# 07_FPGA_banks_3_4_5.net
KiCad netlist of a schematic drawn in Altium Designer
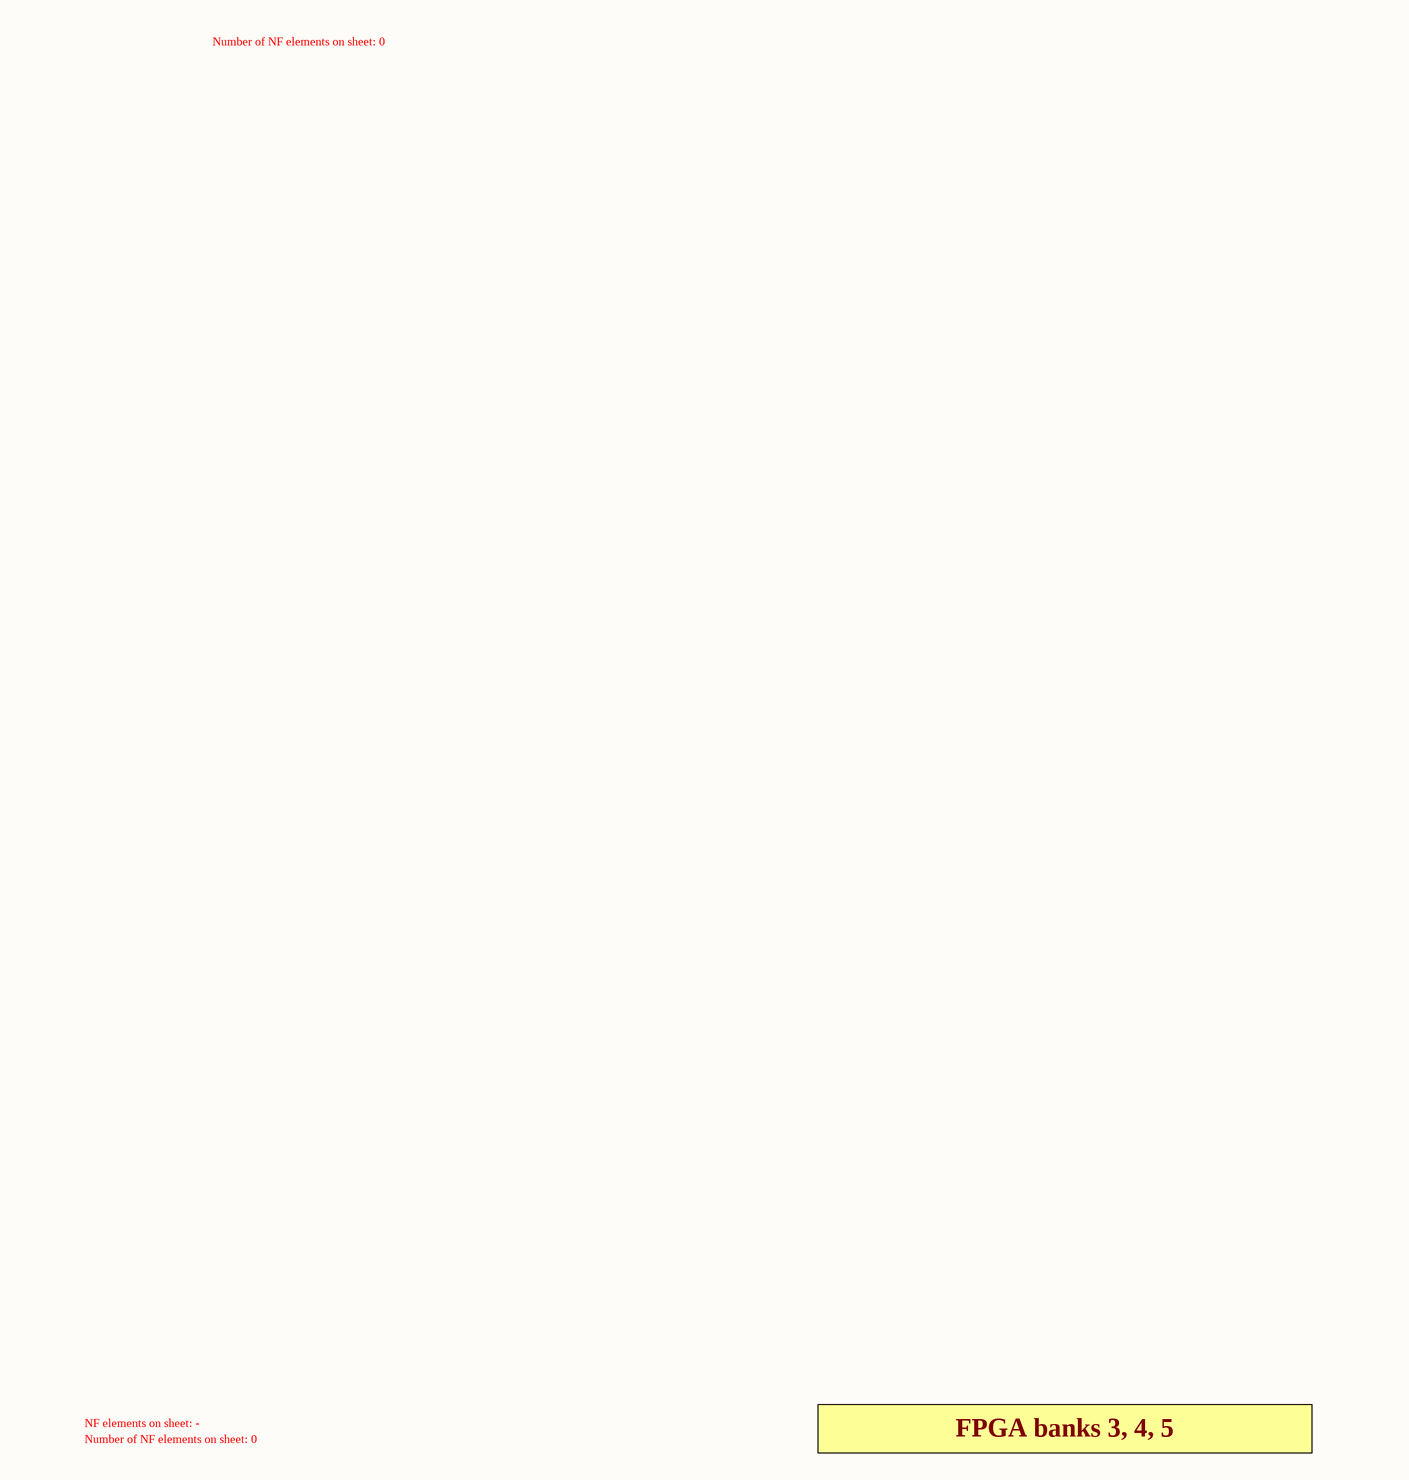
[diagram p0: 07_FPGA_banks_3_4_5.SchDoc, top]
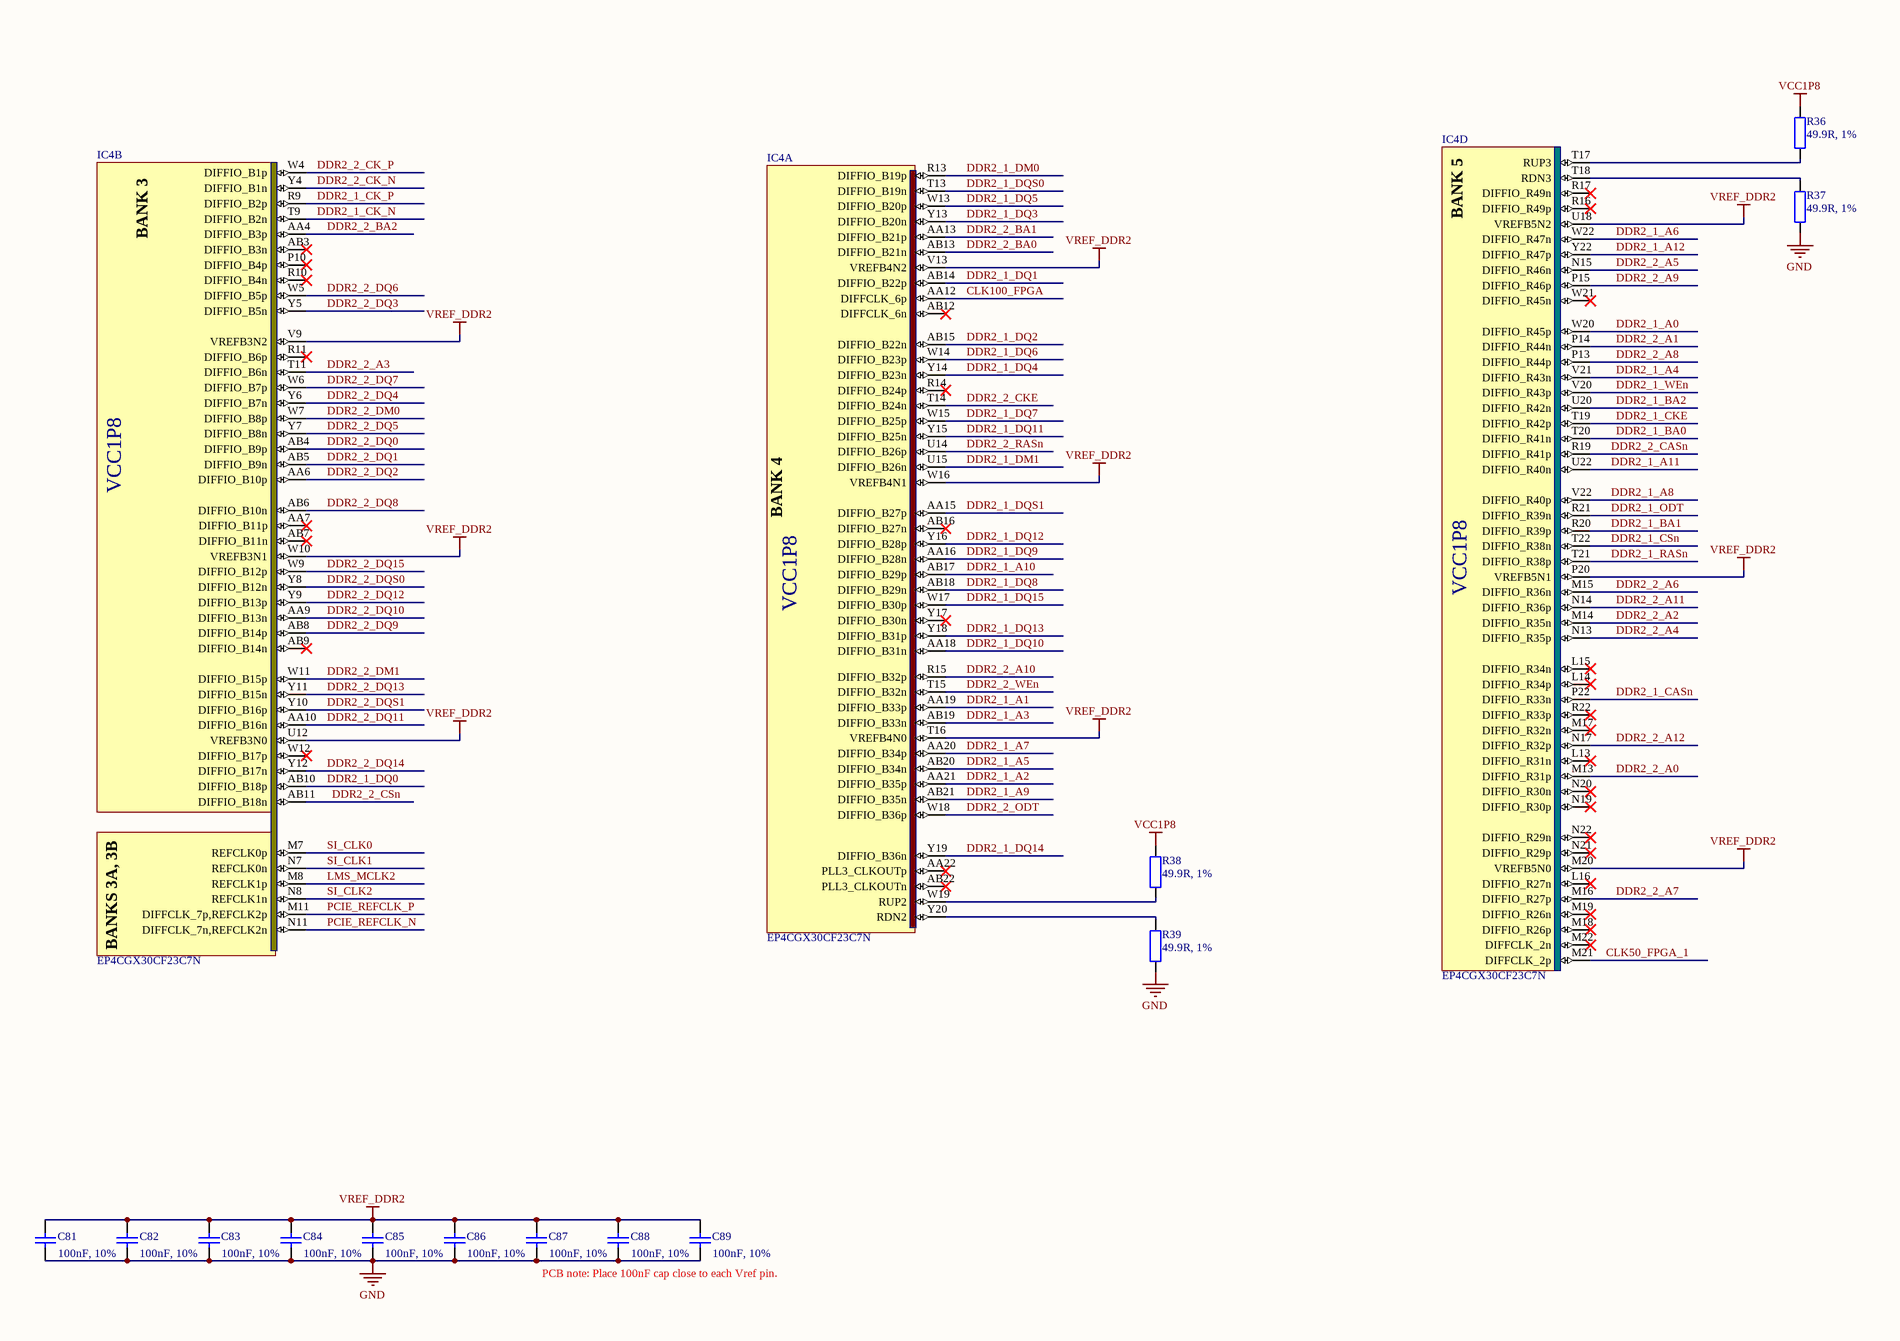
[diagram p1: 07_FPGA_banks_3_4_5.SchDoc, bottom]

(export (version "E")
  (design (tool "Eeschema 10.0.6"))
  (components
    (comp (ref "C81")
      (value "100nF, 10%")
      (footprint "LimeMicroAltiumLib_pcbLib:CAP0402")
      (fields
        (field (name "TOLERANCE") "10 %")
        (field (name "MANUFACTURER") "Murata")
        (field (name "MANUFACTURER PART NUMBER") "GRM155R71C104KA88D")
      )
      (libsource (lib "LimeFPGAboard_schLib") (part "Cap_0603"))
    )
    (comp (ref "C82")
      (value "100nF, 10%")
      (footprint "LimeMicroAltiumLib_pcbLib:CAP0402")
      (fields
        (field (name "TOLERANCE") "10 %")
        (field (name "MANUFACTURER") "Murata")
        (field (name "MANUFACTURER PART NUMBER") "GRM155R71C104KA88D")
      )
      (libsource (lib "LimeFPGAboard_schLib") (part "Cap_0603"))
    )
    (comp (ref "C83")
      (value "100nF, 10%")
      (footprint "LimeMicroAltiumLib_pcbLib:CAP0402")
      (fields
        (field (name "TOLERANCE") "10 %")
        (field (name "MANUFACTURER") "Murata")
        (field (name "MANUFACTURER PART NUMBER") "GRM155R71C104KA88D")
      )
      (libsource (lib "LimeFPGAboard_schLib") (part "Cap_0603"))
    )
    (comp (ref "C84")
      (value "100nF, 10%")
      (footprint "LimeMicroAltiumLib_pcbLib:CAP0402")
      (fields
        (field (name "TOLERANCE") "10 %")
        (field (name "MANUFACTURER") "Murata")
        (field (name "MANUFACTURER PART NUMBER") "GRM155R71C104KA88D")
      )
      (libsource (lib "LimeFPGAboard_schLib") (part "Cap_0603"))
    )
    (comp (ref "C85")
      (value "100nF, 10%")
      (footprint "LimeMicroAltiumLib_pcbLib:CAP0402")
      (fields
        (field (name "TOLERANCE") "10 %")
        (field (name "MANUFACTURER") "Murata")
        (field (name "MANUFACTURER PART NUMBER") "GRM155R71C104KA88D")
      )
      (libsource (lib "LimeFPGAboard_schLib") (part "Cap_0603"))
    )
    (comp (ref "C86")
      (value "100nF, 10%")
      (footprint "LimeMicroAltiumLib_pcbLib:CAP0402")
      (fields
        (field (name "TOLERANCE") "10 %")
        (field (name "MANUFACTURER") "Murata")
        (field (name "MANUFACTURER PART NUMBER") "GRM155R71C104KA88D")
      )
      (libsource (lib "LimeFPGAboard_schLib") (part "Cap_0603"))
    )
    (comp (ref "C87")
      (value "100nF, 10%")
      (footprint "LimeMicroAltiumLib_pcbLib:CAP0402")
      (fields
        (field (name "TOLERANCE") "10 %")
        (field (name "MANUFACTURER") "Murata")
        (field (name "MANUFACTURER PART NUMBER") "GRM155R71C104KA88D")
      )
      (libsource (lib "LimeFPGAboard_schLib") (part "Cap_0603"))
    )
    (comp (ref "C88")
      (value "100nF, 10%")
      (footprint "LimeMicroAltiumLib_pcbLib:CAP0402")
      (fields
        (field (name "TOLERANCE") "10 %")
        (field (name "MANUFACTURER") "Murata")
        (field (name "MANUFACTURER PART NUMBER") "GRM155R71C104KA88D")
      )
      (libsource (lib "LimeFPGAboard_schLib") (part "Cap_0603"))
    )
    (comp (ref "C89")
      (value "100nF, 10%")
      (footprint "LimeMicroAltiumLib_pcbLib:CAP0402")
      (fields
        (field (name "TOLERANCE") "10 %")
        (field (name "MANUFACTURER") "Murata")
        (field (name "MANUFACTURER PART NUMBER") "GRM155R71C104KA88D")
      )
      (libsource (lib "LimeFPGAboard_schLib") (part "Cap_0603"))
    )
    (comp (ref "IC4")
      (value "EP4CGX30CF23C7N")
      (footprint "LimeMicroAltiumLib_pcbLib:ALTR-FBGA484_A-200")
      (fields (field (name "MANUFACTURER") "Altera"))
      (libsource (lib "LimeMicroAltiumLib_schLib") (part "EP4CGX30CF23C7N"))
    )
    (comp (ref "R36")
      (value "49.9R, 1%")
      (footprint "LimeMicroAltiumLib_pcbLib:RES0402")
      (fields
        (field (name "TOLERANCE") "±1%")
        (field (name "MANUFACTURER") "Samsung Electro-Mechanics America, Inc.")
        (field (name "MANUFACTURER PART NUMBER") "RC1005F49R9CS")
      )
      (libsource (lib "LimeMicroAltiumLib_schLib") (part "Res_0402"))
    )
    (comp (ref "R37")
      (value "49.9R, 1%")
      (footprint "LimeMicroAltiumLib_pcbLib:RES0402")
      (fields
        (field (name "TOLERANCE") "±1%")
        (field (name "MANUFACTURER") "Samsung Electro-Mechanics America, Inc.")
        (field (name "MANUFACTURER PART NUMBER") "RC1005F49R9CS")
      )
      (libsource (lib "LimeMicroAltiumLib_schLib") (part "Res_0402"))
    )
    (comp (ref "R38")
      (value "49.9R, 1%")
      (footprint "LimeMicroAltiumLib_pcbLib:RES0402")
      (fields
        (field (name "TOLERANCE") "±1%")
        (field (name "MANUFACTURER") "Samsung Electro-Mechanics America, Inc.")
        (field (name "MANUFACTURER PART NUMBER") "RC1005F49R9CS")
      )
      (libsource (lib "LimeMicroAltiumLib_schLib") (part "Res_0402"))
    )
    (comp (ref "R39")
      (value "49.9R, 1%")
      (footprint "LimeMicroAltiumLib_pcbLib:RES0402")
      (fields
        (field (name "TOLERANCE") "±1%")
        (field (name "MANUFACTURER") "Samsung Electro-Mechanics America, Inc.")
        (field (name "MANUFACTURER PART NUMBER") "RC1005F49R9CS")
      )
      (libsource (lib "LimeMicroAltiumLib_schLib") (part "Res_0402"))
    )
  )
  (nets
    (net (code "1") (name "/CLK50_FPGA_1") (class "Default")
      (node (ref "IC4") (pin "M21") (pinfunction "DIFFCLK_2p_M21") (pintype "bidirectional"))
    )
    (net (code "2") (name "/CLK100_FPGA") (class "Default")
      (node (ref "IC4") (pin "AA12") (pinfunction "DIFFCLK_6p_AA12") (pintype "bidirectional"))
    )
    (net (code "3") (name "/DDR2_1_A0") (class "Default")
      (node (ref "IC4") (pin "W20") (pinfunction "DIFFIO_R45p_W20") (pintype "bidirectional"))
    )
    (net (code "4") (name "/DDR2_1_A1") (class "Default")
      (node (ref "IC4") (pin "AA19") (pinfunction "DIFFIO_B33p_AA19") (pintype "bidirectional"))
    )
    (net (code "5") (name "/DDR2_1_A2") (class "Default")
      (node (ref "IC4") (pin "AA21") (pinfunction "DIFFIO_B35p_AA21") (pintype "bidirectional"))
    )
    (net (code "6") (name "/DDR2_1_A3") (class "Default")
      (node (ref "IC4") (pin "AB19") (pinfunction "DIFFIO_B33n_AB19") (pintype "bidirectional"))
    )
    (net (code "7") (name "/DDR2_1_A4") (class "Default")
      (node (ref "IC4") (pin "V21") (pinfunction "DIFFIO_R43n_V21") (pintype "bidirectional"))
    )
    (net (code "8") (name "/DDR2_1_A5") (class "Default")
      (node (ref "IC4") (pin "AB20") (pinfunction "DIFFIO_B34n_AB20") (pintype "bidirectional"))
    )
    (net (code "9") (name "/DDR2_1_A6") (class "Default")
      (node (ref "IC4") (pin "W22") (pinfunction "DIFFIO_R47n_W22") (pintype "bidirectional"))
    )
    (net (code "10") (name "/DDR2_1_A7") (class "Default")
      (node (ref "IC4") (pin "AA20") (pinfunction "DIFFIO_B34p_AA20") (pintype "bidirectional"))
    )
    (net (code "11") (name "/DDR2_1_A8") (class "Default")
      (node (ref "IC4") (pin "V22") (pinfunction "DIFFIO_R40p_V22") (pintype "bidirectional"))
    )
    (net (code "12") (name "/DDR2_1_A9") (class "Default")
      (node (ref "IC4") (pin "AB21") (pinfunction "DIFFIO_B35n_AB21") (pintype "bidirectional"))
    )
    (net (code "13") (name "/DDR2_1_A10") (class "Default")
      (node (ref "IC4") (pin "AB17") (pinfunction "DIFFIO_B29p_AB17") (pintype "bidirectional"))
    )
    (net (code "14") (name "/DDR2_1_A11") (class "Default")
      (node (ref "IC4") (pin "U22") (pinfunction "DIFFIO_R40n_U22") (pintype "bidirectional"))
    )
    (net (code "15") (name "/DDR2_1_A12") (class "Default")
      (node (ref "IC4") (pin "Y22") (pinfunction "DIFFIO_R47p_Y22") (pintype "bidirectional"))
    )
    (net (code "16") (name "/DDR2_1_BA0") (class "Default")
      (node (ref "IC4") (pin "T20") (pinfunction "DIFFIO_R41n_T20") (pintype "bidirectional"))
    )
    (net (code "17") (name "/DDR2_1_BA1") (class "Default")
      (node (ref "IC4") (pin "R20") (pinfunction "DIFFIO_R39p_R20") (pintype "bidirectional"))
    )
    (net (code "18") (name "/DDR2_1_BA2") (class "Default")
      (node (ref "IC4") (pin "U20") (pinfunction "DIFFIO_R42n_U20") (pintype "bidirectional"))
    )
    (net (code "19") (name "/DDR2_1_CASn") (class "Default")
      (node (ref "IC4") (pin "P22") (pinfunction "DIFFIO_R33n_P22") (pintype "bidirectional"))
    )
    (net (code "20") (name "/DDR2_1_CKE") (class "Default")
      (node (ref "IC4") (pin "T19") (pinfunction "DIFFIO_R42p_T19") (pintype "bidirectional"))
    )
    (net (code "21") (name "/DDR2_1_CK_N") (class "Default")
      (node (ref "IC4") (pin "T9") (pinfunction "DIFFIO_B2n_T9") (pintype "bidirectional"))
    )
    (net (code "22") (name "/DDR2_1_CK_P") (class "Default")
      (node (ref "IC4") (pin "R9") (pinfunction "DIFFIO_B2p_R9") (pintype "bidirectional"))
    )
    (net (code "23") (name "/DDR2_1_CSn") (class "Default")
      (node (ref "IC4") (pin "T22") (pinfunction "DIFFIO_R38n_T22") (pintype "bidirectional"))
    )
    (net (code "24") (name "/DDR2_1_DM0") (class "Default")
      (node (ref "IC4") (pin "R13") (pinfunction "DIFFIO_B19p_R13") (pintype "bidirectional"))
    )
    (net (code "25") (name "/DDR2_1_DM1") (class "Default")
      (node (ref "IC4") (pin "U15") (pinfunction "DIFFIO_B26n_U15") (pintype "bidirectional"))
    )
    (net (code "26") (name "/DDR2_1_DQ0") (class "Default")
      (node (ref "IC4") (pin "AB10") (pinfunction "DIFFIO_B18p_AB10") (pintype "bidirectional"))
    )
    (net (code "27") (name "/DDR2_1_DQ1") (class "Default")
      (node (ref "IC4") (pin "AB14") (pinfunction "DIFFIO_B22p_AB14") (pintype "bidirectional"))
    )
    (net (code "28") (name "/DDR2_1_DQ2") (class "Default")
      (node (ref "IC4") (pin "AB15") (pinfunction "DIFFIO_B22n_AB15") (pintype "bidirectional"))
    )
    (net (code "29") (name "/DDR2_1_DQ3") (class "Default")
      (node (ref "IC4") (pin "Y13") (pinfunction "DIFFIO_B20n_Y13") (pintype "bidirectional"))
    )
    (net (code "30") (name "/DDR2_1_DQ4") (class "Default")
      (node (ref "IC4") (pin "Y14") (pinfunction "DIFFIO_B23n_Y14") (pintype "bidirectional"))
    )
    (net (code "31") (name "/DDR2_1_DQ5") (class "Default")
      (node (ref "IC4") (pin "W13") (pinfunction "DIFFIO_B20p_W13") (pintype "bidirectional"))
    )
    (net (code "32") (name "/DDR2_1_DQ6") (class "Default")
      (node (ref "IC4") (pin "W14") (pinfunction "DIFFIO_B23p_W14") (pintype "bidirectional"))
    )
    (net (code "33") (name "/DDR2_1_DQ7") (class "Default")
      (node (ref "IC4") (pin "W15") (pinfunction "DIFFIO_B25p_W15") (pintype "bidirectional"))
    )
    (net (code "34") (name "/DDR2_1_DQ8") (class "Default")
      (node (ref "IC4") (pin "AB18") (pinfunction "DIFFIO_B29n_AB18") (pintype "bidirectional"))
    )
    (net (code "35") (name "/DDR2_1_DQ9") (class "Default")
      (node (ref "IC4") (pin "AA16") (pinfunction "DIFFIO_B28n_AA16") (pintype "bidirectional"))
    )
    (net (code "36") (name "/DDR2_1_DQ10") (class "Default")
      (node (ref "IC4") (pin "AA18") (pinfunction "DIFFIO_B31n_AA18") (pintype "bidirectional"))
    )
    (net (code "37") (name "/DDR2_1_DQ11") (class "Default")
      (node (ref "IC4") (pin "Y15") (pinfunction "DIFFIO_B25n_Y15") (pintype "bidirectional"))
    )
    (net (code "38") (name "/DDR2_1_DQ12") (class "Default")
      (node (ref "IC4") (pin "Y16") (pinfunction "DIFFIO_B28p_Y16") (pintype "bidirectional"))
    )
    (net (code "39") (name "/DDR2_1_DQ13") (class "Default")
      (node (ref "IC4") (pin "Y18") (pinfunction "DIFFIO_B31p_Y18") (pintype "bidirectional"))
    )
    (net (code "40") (name "/DDR2_1_DQ14") (class "Default")
      (node (ref "IC4") (pin "Y19") (pinfunction "DIFFIO_B36n_Y19") (pintype "bidirectional"))
    )
    (net (code "41") (name "/DDR2_1_DQ15") (class "Default")
      (node (ref "IC4") (pin "W17") (pinfunction "DIFFIO_B30p_W17") (pintype "bidirectional"))
    )
    (net (code "42") (name "/DDR2_1_DQS0") (class "Default")
      (node (ref "IC4") (pin "T13") (pinfunction "DIFFIO_B19n_T13") (pintype "bidirectional"))
    )
    (net (code "43") (name "/DDR2_1_DQS1") (class "Default")
      (node (ref "IC4") (pin "AA15") (pinfunction "DIFFIO_B27p_AA15") (pintype "bidirectional"))
    )
    (net (code "44") (name "/DDR2_1_ODT") (class "Default")
      (node (ref "IC4") (pin "R21") (pinfunction "DIFFIO_R39n_R21") (pintype "bidirectional"))
    )
    (net (code "45") (name "/DDR2_1_RASn") (class "Default")
      (node (ref "IC4") (pin "T21") (pinfunction "DIFFIO_R38p_T21") (pintype "bidirectional"))
    )
    (net (code "46") (name "/DDR2_1_WEn") (class "Default")
      (node (ref "IC4") (pin "V20") (pinfunction "DIFFIO_R43p_V20") (pintype "bidirectional"))
    )
    (net (code "47") (name "/DDR2_2_A0") (class "Default")
      (node (ref "IC4") (pin "M13") (pinfunction "DIFFIO_R31p_M13") (pintype "bidirectional"))
    )
    (net (code "48") (name "/DDR2_2_A1") (class "Default")
      (node (ref "IC4") (pin "P14") (pinfunction "DIFFIO_R44n_P14") (pintype "bidirectional"))
    )
    (net (code "49") (name "/DDR2_2_A2") (class "Default")
      (node (ref "IC4") (pin "M14") (pinfunction "DIFFIO_R35n_M14") (pintype "bidirectional"))
    )
    (net (code "50") (name "/DDR2_2_A3") (class "Default")
      (node (ref "IC4") (pin "T11") (pinfunction "DIFFIO_B6n_T11") (pintype "bidirectional"))
    )
    (net (code "51") (name "/DDR2_2_A4") (class "Default")
      (node (ref "IC4") (pin "N13") (pinfunction "DIFFIO_R35p_N13") (pintype "bidirectional"))
    )
    (net (code "52") (name "/DDR2_2_A5") (class "Default")
      (node (ref "IC4") (pin "N15") (pinfunction "DIFFIO_R46n_N15") (pintype "bidirectional"))
    )
    (net (code "53") (name "/DDR2_2_A6") (class "Default")
      (node (ref "IC4") (pin "M15") (pinfunction "DIFFIO_R36n_M15") (pintype "bidirectional"))
    )
    (net (code "54") (name "/DDR2_2_A7") (class "Default")
      (node (ref "IC4") (pin "M16") (pinfunction "DIFFIO_R27p_M16") (pintype "bidirectional"))
    )
    (net (code "55") (name "/DDR2_2_A8") (class "Default")
      (node (ref "IC4") (pin "P13") (pinfunction "DIFFIO_R44p_P13") (pintype "bidirectional"))
    )
    (net (code "56") (name "/DDR2_2_A9") (class "Default")
      (node (ref "IC4") (pin "P15") (pinfunction "DIFFIO_R46p_P15") (pintype "bidirectional"))
    )
    (net (code "57") (name "/DDR2_2_A10") (class "Default")
      (node (ref "IC4") (pin "R15") (pinfunction "DIFFIO_B32p_R15") (pintype "bidirectional"))
    )
    (net (code "58") (name "/DDR2_2_A11") (class "Default")
      (node (ref "IC4") (pin "N14") (pinfunction "DIFFIO_R36p_N14") (pintype "bidirectional"))
    )
    (net (code "59") (name "/DDR2_2_A12") (class "Default")
      (node (ref "IC4") (pin "N17") (pinfunction "DIFFIO_R32p_N17") (pintype "bidirectional"))
    )
    (net (code "60") (name "/DDR2_2_BA0") (class "Default")
      (node (ref "IC4") (pin "AB13") (pinfunction "DIFFIO_B21n_AB13") (pintype "bidirectional"))
    )
    (net (code "61") (name "/DDR2_2_BA1") (class "Default")
      (node (ref "IC4") (pin "AA13") (pinfunction "DIFFIO_B21p_AA13") (pintype "bidirectional"))
    )
    (net (code "62") (name "/DDR2_2_BA2") (class "Default")
      (node (ref "IC4") (pin "AA4") (pinfunction "DIFFIO_B3p_AA4") (pintype "bidirectional"))
    )
    (net (code "63") (name "/DDR2_2_CASn") (class "Default")
      (node (ref "IC4") (pin "R19") (pinfunction "DIFFIO_R41p_R19") (pintype "bidirectional"))
    )
    (net (code "64") (name "/DDR2_2_CKE") (class "Default")
      (node (ref "IC4") (pin "T14") (pinfunction "DIFFIO_B24n_T14") (pintype "bidirectional"))
    )
    (net (code "65") (name "/DDR2_2_CK_N") (class "Default")
      (node (ref "IC4") (pin "Y4") (pinfunction "DIFFIO_B1n_Y4") (pintype "bidirectional"))
    )
    (net (code "66") (name "/DDR2_2_CK_P") (class "Default")
      (node (ref "IC4") (pin "W4") (pinfunction "DIFFIO_B1p_W4") (pintype "bidirectional"))
    )
    (net (code "67") (name "/DDR2_2_CSn") (class "Default")
      (node (ref "IC4") (pin "AB11") (pinfunction "DIFFIO_B18n_AB11") (pintype "bidirectional"))
    )
    (net (code "68") (name "/DDR2_2_DM0") (class "Default")
      (node (ref "IC4") (pin "W7") (pinfunction "DIFFIO_B8p_W7") (pintype "bidirectional"))
    )
    (net (code "69") (name "/DDR2_2_DM1") (class "Default")
      (node (ref "IC4") (pin "W11") (pinfunction "DIFFIO_B15p_W11") (pintype "bidirectional"))
    )
    (net (code "70") (name "/DDR2_2_DQ0") (class "Default")
      (node (ref "IC4") (pin "AB4") (pinfunction "DIFFIO_B9p_AB4") (pintype "bidirectional"))
    )
    (net (code "71") (name "/DDR2_2_DQ1") (class "Default")
      (node (ref "IC4") (pin "AB5") (pinfunction "DIFFIO_B9n_AB5") (pintype "bidirectional"))
    )
    (net (code "72") (name "/DDR2_2_DQ2") (class "Default")
      (node (ref "IC4") (pin "AA6") (pinfunction "DIFFIO_B10p_AA6") (pintype "bidirectional"))
    )
    (net (code "73") (name "/DDR2_2_DQ3") (class "Default")
      (node (ref "IC4") (pin "Y5") (pinfunction "DIFFIO_B5n_Y5") (pintype "bidirectional"))
    )
    (net (code "74") (name "/DDR2_2_DQ4") (class "Default")
      (node (ref "IC4") (pin "Y6") (pinfunction "DIFFIO_B7n_Y6") (pintype "bidirectional"))
    )
    (net (code "75") (name "/DDR2_2_DQ5") (class "Default")
      (node (ref "IC4") (pin "Y7") (pinfunction "DIFFIO_B8n_Y7") (pintype "bidirectional"))
    )
    (net (code "76") (name "/DDR2_2_DQ6") (class "Default")
      (node (ref "IC4") (pin "W5") (pinfunction "DIFFIO_B5p_W5") (pintype "bidirectional"))
    )
    (net (code "77") (name "/DDR2_2_DQ7") (class "Default")
      (node (ref "IC4") (pin "W6") (pinfunction "DIFFIO_B7p_W6") (pintype "bidirectional"))
    )
    (net (code "78") (name "/DDR2_2_DQ8") (class "Default")
      (node (ref "IC4") (pin "AB6") (pinfunction "DIFFIO_B10n_AB6") (pintype "bidirectional"))
    )
    (net (code "79") (name "/DDR2_2_DQ9") (class "Default")
      (node (ref "IC4") (pin "AB8") (pinfunction "DIFFIO_B14p_AB8") (pintype "bidirectional"))
    )
    (net (code "80") (name "/DDR2_2_DQ10") (class "Default")
      (node (ref "IC4") (pin "AA9") (pinfunction "DIFFIO_B13n_AA9") (pintype "bidirectional"))
    )
    (net (code "81") (name "/DDR2_2_DQ11") (class "Default")
      (node (ref "IC4") (pin "AA10") (pinfunction "DIFFIO_B16n_AA10") (pintype "bidirectional"))
    )
    (net (code "82") (name "/DDR2_2_DQ12") (class "Default")
      (node (ref "IC4") (pin "Y9") (pinfunction "DIFFIO_B13p_Y9") (pintype "bidirectional"))
    )
    (net (code "83") (name "/DDR2_2_DQ13") (class "Default")
      (node (ref "IC4") (pin "Y11") (pinfunction "DIFFIO_B15n_Y11") (pintype "bidirectional"))
    )
    (net (code "84") (name "/DDR2_2_DQ14") (class "Default")
      (node (ref "IC4") (pin "Y12") (pinfunction "DIFFIO_B17n_Y12") (pintype "bidirectional"))
    )
    (net (code "85") (name "/DDR2_2_DQ15") (class "Default")
      (node (ref "IC4") (pin "W9") (pinfunction "DIFFIO_B12p_W9") (pintype "bidirectional"))
    )
    (net (code "86") (name "/DDR2_2_DQS0") (class "Default")
      (node (ref "IC4") (pin "Y8") (pinfunction "DIFFIO_B12n_Y8") (pintype "bidirectional"))
    )
    (net (code "87") (name "/DDR2_2_DQS1") (class "Default")
      (node (ref "IC4") (pin "Y10") (pinfunction "DIFFIO_B16p_Y10") (pintype "bidirectional"))
    )
    (net (code "88") (name "/DDR2_2_ODT") (class "Default")
      (node (ref "IC4") (pin "W18") (pinfunction "DIFFIO_B36p_W18") (pintype "bidirectional"))
    )
    (net (code "89") (name "/DDR2_2_RASn") (class "Default")
      (node (ref "IC4") (pin "U14") (pinfunction "DIFFIO_B26p_U14") (pintype "bidirectional"))
    )
    (net (code "90") (name "/DDR2_2_WEn") (class "Default")
      (node (ref "IC4") (pin "T15") (pinfunction "DIFFIO_B32n_T15") (pintype "bidirectional"))
    )
    (net (code "91") (name "/LMS_MCLK2") (class "Default")
      (node (ref "IC4") (pin "M8") (pinfunction "REFCLK1p_M8") (pintype "bidirectional"))
    )
    (net (code "92") (name "/PCIE_REFCLK_N") (class "Default")
      (node (ref "IC4") (pin "N11") (pinfunction "DIFFCLK_7n,REFCLK2n_N11") (pintype "bidirectional"))
    )
    (net (code "93") (name "/PCIE_REFCLK_P") (class "Default")
      (node (ref "IC4") (pin "M11") (pinfunction "DIFFCLK_7p,REFCLK2p_M11") (pintype "bidirectional"))
    )
    (net (code "94") (name "/SI_CLK0") (class "Default")
      (node (ref "IC4") (pin "M7") (pinfunction "REFCLK0p_M7") (pintype "bidirectional"))
    )
    (net (code "95") (name "/SI_CLK1") (class "Default")
      (node (ref "IC4") (pin "N7") (pinfunction "REFCLK0n_N7") (pintype "bidirectional"))
    )
    (net (code "96") (name "/SI_CLK2") (class "Default")
      (node (ref "IC4") (pin "N8") (pinfunction "REFCLK1n_N8") (pintype "bidirectional"))
    )
    (net (code "97") (name "GND") (class "Default")
      (node (ref "C81") (pin "2") (pinfunction "2_2") (pintype "passive"))
      (node (ref "C82") (pin "2") (pinfunction "2_2") (pintype "passive"))
      (node (ref "C83") (pin "2") (pinfunction "2_2") (pintype "passive"))
      (node (ref "C84") (pin "2") (pinfunction "2_2") (pintype "passive"))
      (node (ref "C85") (pin "2") (pinfunction "2_2") (pintype "passive"))
      (node (ref "C86") (pin "2") (pinfunction "2_2") (pintype "passive"))
      (node (ref "C87") (pin "2") (pinfunction "2_2") (pintype "passive"))
      (node (ref "C88") (pin "2") (pinfunction "2_2") (pintype "passive"))
      (node (ref "C89") (pin "2") (pinfunction "2_2") (pintype "passive"))
      (node (ref "R37") (pin "1") (pinfunction "1_1") (pintype "passive"))
      (node (ref "R39") (pin "1") (pinfunction "1_1") (pintype "passive"))
    )
    (net (code "98") (name "Net-(IC4A-RDN2)") (class "Default")
      (node (ref "IC4") (pin "Y20") (pinfunction "RDN2_Y20") (pintype "bidirectional"))
      (node (ref "R39") (pin "2") (pinfunction "2_2") (pintype "passive"))
    )
    (net (code "99") (name "Net-(IC4A-RUP2)") (class "Default")
      (node (ref "IC4") (pin "W19") (pinfunction "RUP2_W19") (pintype "bidirectional"))
      (node (ref "R38") (pin "1") (pinfunction "1_1") (pintype "passive"))
    )
    (net (code "100") (name "Net-(IC4D-RDN3)") (class "Default")
      (node (ref "IC4") (pin "T18") (pinfunction "RDN3_T18") (pintype "bidirectional"))
      (node (ref "R37") (pin "2") (pinfunction "2_2") (pintype "passive"))
    )
    (net (code "101") (name "Net-(IC4D-RUP3)") (class "Default")
      (node (ref "IC4") (pin "T17") (pinfunction "RUP3_T17") (pintype "bidirectional"))
      (node (ref "R36") (pin "1") (pinfunction "1_1") (pintype "passive"))
    )
    (net (code "102") (name "VCC1P8") (class "Default")
      (node (ref "R36") (pin "2") (pinfunction "2_2") (pintype "passive"))
      (node (ref "R38") (pin "2") (pinfunction "2_2") (pintype "passive"))
    )
    (net (code "103") (name "VREF_DDR2") (class "Default")
      (node (ref "C81") (pin "1") (pinfunction "1_1") (pintype "passive"))
      (node (ref "C82") (pin "1") (pinfunction "1_1") (pintype "passive"))
      (node (ref "C83") (pin "1") (pinfunction "1_1") (pintype "passive"))
      (node (ref "C84") (pin "1") (pinfunction "1_1") (pintype "passive"))
      (node (ref "C85") (pin "1") (pinfunction "1_1") (pintype "passive"))
      (node (ref "C86") (pin "1") (pinfunction "1_1") (pintype "passive"))
      (node (ref "C87") (pin "1") (pinfunction "1_1") (pintype "passive"))
      (node (ref "C88") (pin "1") (pinfunction "1_1") (pintype "passive"))
      (node (ref "C89") (pin "1") (pinfunction "1_1") (pintype "passive"))
      (node (ref "IC4") (pin "M20") (pinfunction "VREFB5N0_M20") (pintype "bidirectional"))
      (node (ref "IC4") (pin "P20") (pinfunction "VREFB5N1_P20") (pintype "bidirectional"))
      (node (ref "IC4") (pin "T16") (pinfunction "VREFB4N0_T16") (pintype "bidirectional"))
      (node (ref "IC4") (pin "U12") (pinfunction "VREFB3N0_U12") (pintype "bidirectional"))
      (node (ref "IC4") (pin "U18") (pinfunction "VREFB5N2_U18") (pintype "bidirectional"))
      (node (ref "IC4") (pin "V13") (pinfunction "VREFB4N2_V13") (pintype "bidirectional"))
      (node (ref "IC4") (pin "V9") (pinfunction "VREFB3N2_V9") (pintype "bidirectional"))
      (node (ref "IC4") (pin "W10") (pinfunction "VREFB3N1_W10") (pintype "bidirectional"))
      (node (ref "IC4") (pin "W16") (pinfunction "VREFB4N1_W16") (pintype "bidirectional"))
    )
    (net (code "104") (name "unconnected-(IC4A-DIFFCLK_6n-PadAB12)") (class "Default")
      (node (ref "IC4") (pin "AB12") (pinfunction "DIFFCLK_6n_AB12") (pintype "bidirectional+no_connect"))
    )
    (net (code "105") (name "unconnected-(IC4A-DIFFIO_B24p-PadR14)") (class "Default")
      (node (ref "IC4") (pin "R14") (pinfunction "DIFFIO_B24p_R14") (pintype "bidirectional+no_connect"))
    )
    (net (code "106") (name "unconnected-(IC4A-DIFFIO_B27n-PadAB16)") (class "Default")
      (node (ref "IC4") (pin "AB16") (pinfunction "DIFFIO_B27n_AB16") (pintype "bidirectional+no_connect"))
    )
    (net (code "107") (name "unconnected-(IC4A-DIFFIO_B30n-PadY17)") (class "Default")
      (node (ref "IC4") (pin "Y17") (pinfunction "DIFFIO_B30n_Y17") (pintype "bidirectional+no_connect"))
    )
    (net (code "108") (name "unconnected-(IC4A-PLL3_CLKOUTn-PadAB22)") (class "Default")
      (node (ref "IC4") (pin "AB22") (pinfunction "PLL3_CLKOUTn_AB22") (pintype "bidirectional+no_connect"))
    )
    (net (code "109") (name "unconnected-(IC4A-PLL3_CLKOUTp-PadAA22)") (class "Default")
      (node (ref "IC4") (pin "AA22") (pinfunction "PLL3_CLKOUTp_AA22") (pintype "bidirectional+no_connect"))
    )
    (net (code "110") (name "unconnected-(IC4B-DIFFIO_B3n-PadAB3)") (class "Default")
      (node (ref "IC4") (pin "AB3") (pinfunction "DIFFIO_B3n_AB3") (pintype "bidirectional+no_connect"))
    )
    (net (code "111") (name "unconnected-(IC4B-DIFFIO_B4n-PadR10)") (class "Default")
      (node (ref "IC4") (pin "R10") (pinfunction "DIFFIO_B4n_R10") (pintype "bidirectional+no_connect"))
    )
    (net (code "112") (name "unconnected-(IC4B-DIFFIO_B4p-PadP10)") (class "Default")
      (node (ref "IC4") (pin "P10") (pinfunction "DIFFIO_B4p_P10") (pintype "bidirectional+no_connect"))
    )
    (net (code "113") (name "unconnected-(IC4B-DIFFIO_B6p-PadR11)") (class "Default")
      (node (ref "IC4") (pin "R11") (pinfunction "DIFFIO_B6p_R11") (pintype "bidirectional+no_connect"))
    )
    (net (code "114") (name "unconnected-(IC4B-DIFFIO_B11n-PadAB7)") (class "Default")
      (node (ref "IC4") (pin "AB7") (pinfunction "DIFFIO_B11n_AB7") (pintype "bidirectional+no_connect"))
    )
    (net (code "115") (name "unconnected-(IC4B-DIFFIO_B11p-PadAA7)") (class "Default")
      (node (ref "IC4") (pin "AA7") (pinfunction "DIFFIO_B11p_AA7") (pintype "bidirectional+no_connect"))
    )
    (net (code "116") (name "unconnected-(IC4B-DIFFIO_B14n-PadAB9)") (class "Default")
      (node (ref "IC4") (pin "AB9") (pinfunction "DIFFIO_B14n_AB9") (pintype "bidirectional+no_connect"))
    )
    (net (code "117") (name "unconnected-(IC4B-DIFFIO_B17p-PadW12)") (class "Default")
      (node (ref "IC4") (pin "W12") (pinfunction "DIFFIO_B17p_W12") (pintype "bidirectional+no_connect"))
    )
    (net (code "118") (name "unconnected-(IC4D-DIFFCLK_2n-PadM22)") (class "Default")
      (node (ref "IC4") (pin "M22") (pinfunction "DIFFCLK_2n_M22") (pintype "bidirectional+no_connect"))
    )
    (net (code "119") (name "unconnected-(IC4D-DIFFIO_R26n-PadM19)") (class "Default")
      (node (ref "IC4") (pin "M19") (pinfunction "DIFFIO_R26n_M19") (pintype "bidirectional+no_connect"))
    )
    (net (code "120") (name "unconnected-(IC4D-DIFFIO_R26p-PadM18)") (class "Default")
      (node (ref "IC4") (pin "M18") (pinfunction "DIFFIO_R26p_M18") (pintype "bidirectional+no_connect"))
    )
    (net (code "121") (name "unconnected-(IC4D-DIFFIO_R27n-PadL16)") (class "Default")
      (node (ref "IC4") (pin "L16") (pinfunction "DIFFIO_R27n_L16") (pintype "bidirectional+no_connect"))
    )
    (net (code "122") (name "unconnected-(IC4D-DIFFIO_R29n-PadN22)") (class "Default")
      (node (ref "IC4") (pin "N22") (pinfunction "DIFFIO_R29n_N22") (pintype "bidirectional+no_connect"))
    )
    (net (code "123") (name "unconnected-(IC4D-DIFFIO_R29p-PadN21)") (class "Default")
      (node (ref "IC4") (pin "N21") (pinfunction "DIFFIO_R29p_N21") (pintype "bidirectional+no_connect"))
    )
    (net (code "124") (name "unconnected-(IC4D-DIFFIO_R30n-PadN20)") (class "Default")
      (node (ref "IC4") (pin "N20") (pinfunction "DIFFIO_R30n_N20") (pintype "bidirectional+no_connect"))
    )
    (net (code "125") (name "unconnected-(IC4D-DIFFIO_R30p-PadN19)") (class "Default")
      (node (ref "IC4") (pin "N19") (pinfunction "DIFFIO_R30p_N19") (pintype "bidirectional+no_connect"))
    )
    (net (code "126") (name "unconnected-(IC4D-DIFFIO_R31n-PadL13)") (class "Default")
      (node (ref "IC4") (pin "L13") (pinfunction "DIFFIO_R31n_L13") (pintype "bidirectional+no_connect"))
    )
    (net (code "127") (name "unconnected-(IC4D-DIFFIO_R32n-PadM17)") (class "Default")
      (node (ref "IC4") (pin "M17") (pinfunction "DIFFIO_R32n_M17") (pintype "bidirectional+no_connect"))
    )
    (net (code "128") (name "unconnected-(IC4D-DIFFIO_R33p-PadR22)") (class "Default")
      (node (ref "IC4") (pin "R22") (pinfunction "DIFFIO_R33p_R22") (pintype "bidirectional+no_connect"))
    )
    (net (code "129") (name "unconnected-(IC4D-DIFFIO_R34n-PadL15)") (class "Default")
      (node (ref "IC4") (pin "L15") (pinfunction "DIFFIO_R34n_L15") (pintype "bidirectional+no_connect"))
    )
    (net (code "130") (name "unconnected-(IC4D-DIFFIO_R34p-PadL14)") (class "Default")
      (node (ref "IC4") (pin "L14") (pinfunction "DIFFIO_R34p_L14") (pintype "bidirectional+no_connect"))
    )
    (net (code "131") (name "unconnected-(IC4D-DIFFIO_R45n-PadW21)") (class "Default")
      (node (ref "IC4") (pin "W21") (pinfunction "DIFFIO_R45n_W21") (pintype "bidirectional+no_connect"))
    )
    (net (code "132") (name "unconnected-(IC4D-DIFFIO_R49n-PadR17)") (class "Default")
      (node (ref "IC4") (pin "R17") (pinfunction "DIFFIO_R49n_R17") (pintype "bidirectional+no_connect"))
    )
    (net (code "133") (name "unconnected-(IC4D-DIFFIO_R49p-PadR16)") (class "Default")
      (node (ref "IC4") (pin "R16") (pinfunction "DIFFIO_R49p_R16") (pintype "bidirectional+no_connect"))
    )
  )
)
